# PiHat.net
KiCad netlist of a schematic drawn in EAGLE
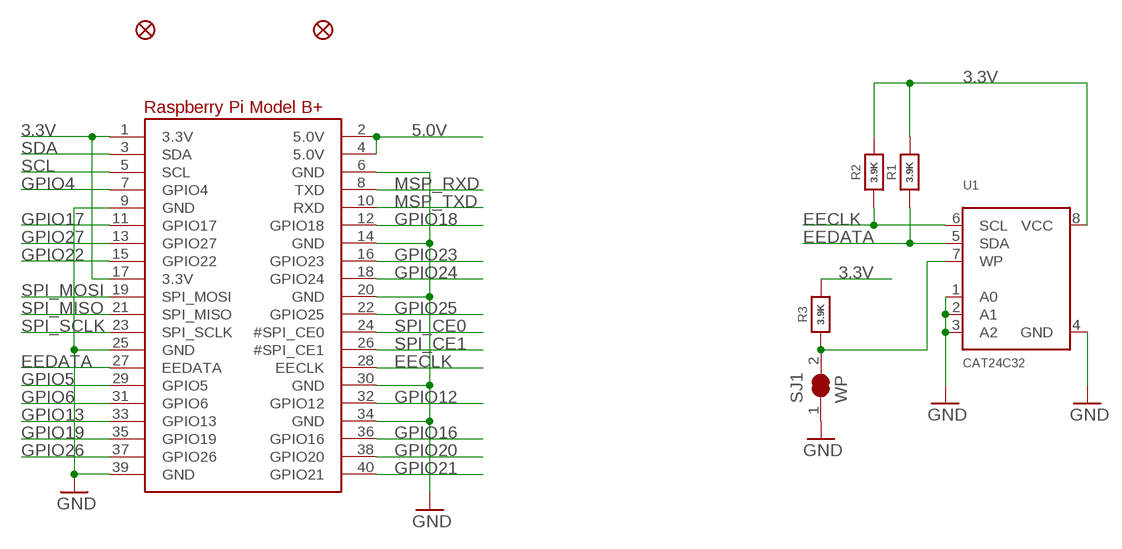
[diagram p0: schematic, sheet 1]
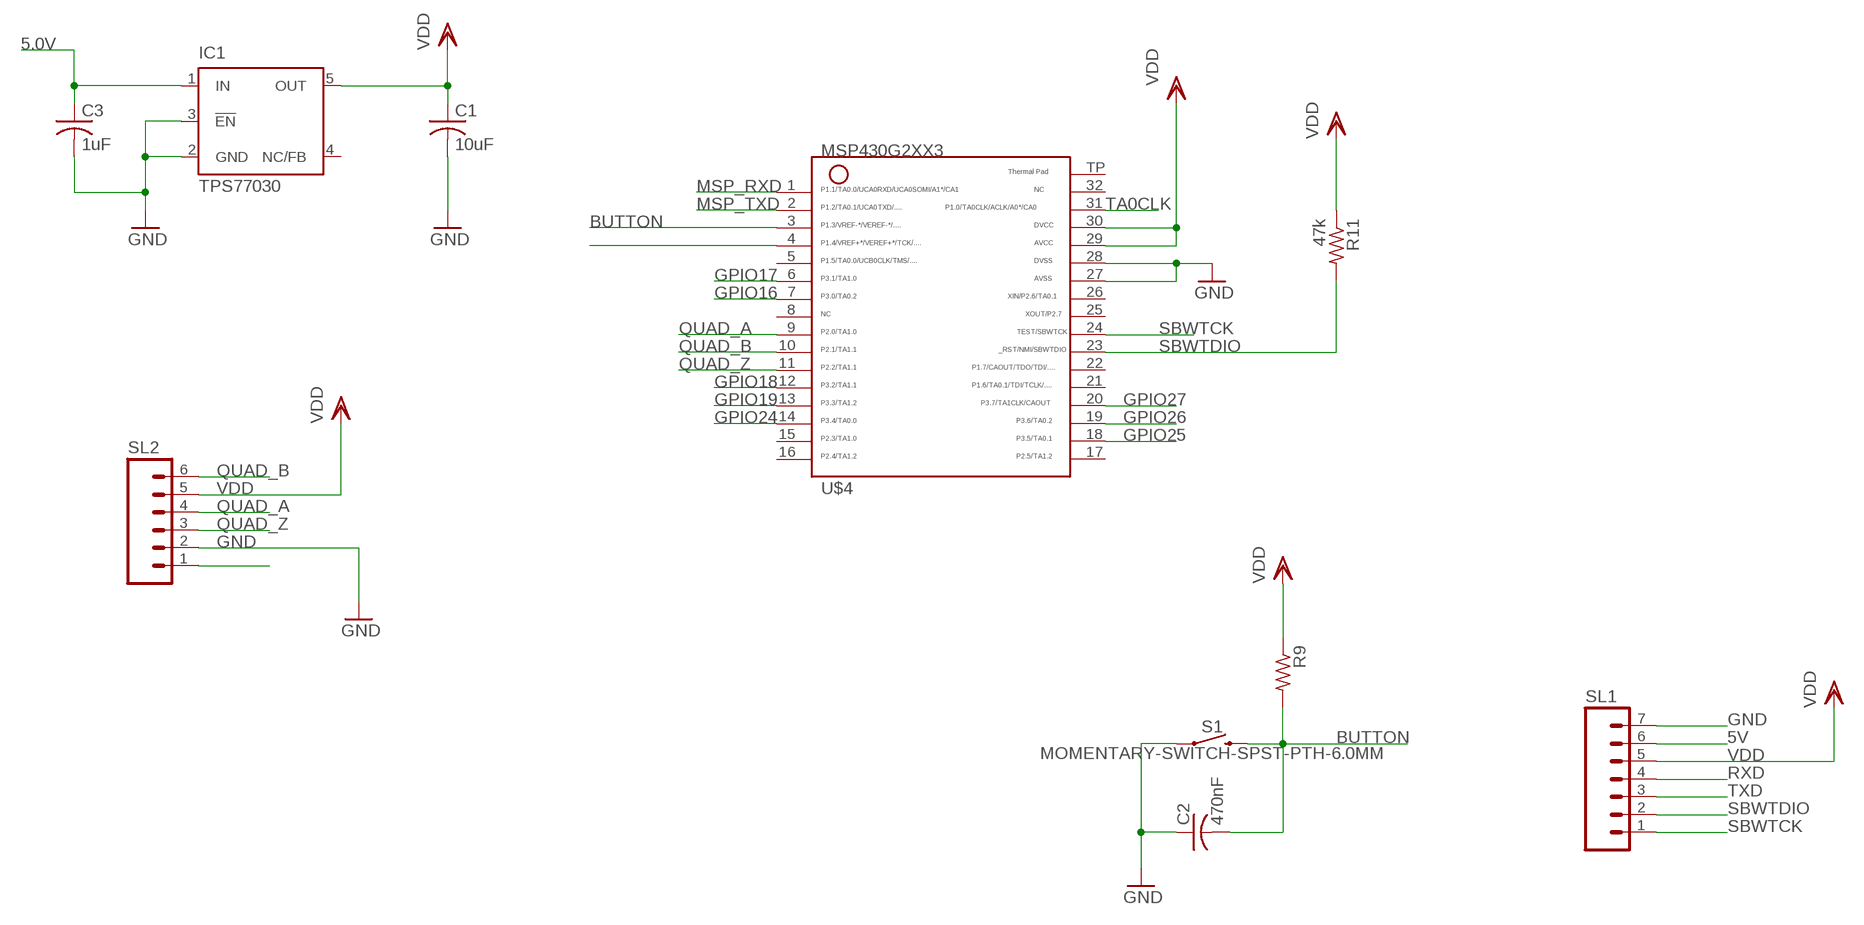
[diagram p1: schematic, sheet 2]

(export (version "E")
  (design (tool "Eeschema 10.0.6"))
  (components
    (comp (ref "FID2")
      (value "FIDUCIAL\"\"")
      (footprint "eagle-import:FIDUCIAL_1MM")
      (libsource (lib "eagle-import") (part "FIDUCIAL{dblquote}{dblquote}"))
    )
    (comp (ref "FID3")
      (value "FIDUCIAL\"\"")
      (footprint "eagle-import:FIDUCIAL_1MM")
      (libsource (lib "eagle-import") (part "FIDUCIAL{dblquote}{dblquote}"))
    )
    (comp (ref "R1")
      (value "3.9K")
      (footprint "eagle-import:0805-NO")
      (libsource (lib "eagle-import") (part "RESISTOR0805_NOOUTLINE"))
    )
    (comp (ref "R2")
      (value "3.9K")
      (footprint "eagle-import:0805-NO")
      (libsource (lib "eagle-import") (part "RESISTOR0805_NOOUTLINE"))
    )
    (comp (ref "R3")
      (value "3.9K")
      (footprint "eagle-import:0805-NO")
      (libsource (lib "eagle-import") (part "RESISTOR0805_NOOUTLINE"))
    )
    (comp (ref "RPI1")
      (value "RASPBERRYPI_BPLUS_HATNOSLOTS")
      (footprint "eagle-import:PI_HAT_NOSLOTS")
      (libsource (lib "eagle-import") (part "RASPBERRYPI_BPLUS_HATNOSLOTS"))
    )
    (comp (ref "SJ1")
      (value "WP")
      (footprint "eagle-import:SOLDERJUMPER_CLOSEDWIRE")
      (libsource (lib "eagle-import") (part "SOLDERJUMPER_CLOSED"))
    )
    (comp (ref "U1")
      (value "CAT24C32")
      (footprint "eagle-import:SOIC8_150MIL")
      (libsource (lib "eagle-import") (part "EEPROM_I2C_SOIC8_GENERIC"))
    )
    (comp (ref "C1")
      (value "10uF")
      (footprint "eagle-import:C1206")
      (libsource (lib "eagle-import") (part "C-USC1206"))
    )
    (comp (ref "C2")
      (value "470nF")
      (footprint "eagle-import:C1206")
      (libsource (lib "eagle-import") (part "C-USC1206"))
    )
    (comp (ref "C3")
      (value "1uF")
      (footprint "eagle-import:C0603")
      (libsource (lib "eagle-import") (part "C-USC0603"))
    )
    (comp (ref "IC1")
      (value "TPS77030")
      (footprint "eagle-import:SOT23-DBV")
      (fields (field (name "MF") "TEXAS INSTRUMENTS") (field (name "MPN") "TPS77030DBVT"))
      (libsource (lib "eagle-import") (part "TPS77030"))
    )
    (comp (ref "R9")
      (value "R-US_R1206")
      (footprint "eagle-import:R1206")
      (libsource (lib "eagle-import") (part "R-US_R1206"))
    )
    (comp (ref "R11")
      (value "47k")
      (footprint "eagle-import:R1206")
      (libsource (lib "eagle-import") (part "R-US_R1206"))
    )
    (comp (ref "S1")
      (value "MOMENTARY-SWITCH-SPST-PTH-6.0MM")
      (footprint "eagle-import:TACTILE_SWITCH_PTH_6.0MM")
      (libsource (lib "eagle-import") (part "MOMENTARY-SWITCH-SPST-PTH-6.0MM"))
    )
    (comp (ref "SL1")
      (value "M07")
      (footprint "eagle-import:07P")
      (libsource (lib "eagle-import") (part "M07"))
    )
    (comp (ref "SL2")
      (value "M06")
      (footprint "eagle-import:06P")
      (libsource (lib "eagle-import") (part "M06"))
    )
    (comp (ref "U$4")
      (value "G2XX3---RHB32")
      (footprint "eagle-import:RHB32")
      (libsource (lib "eagle-import") (part "G2XX3---RHB32"))
    )
  )
  (nets
    (net (code "1") (name "3.3V") (class "Default")
      (node (ref "R1") (pin "2") (pinfunction "2_2") (pintype "passive"))
      (node (ref "R2") (pin "2") (pinfunction "2_2") (pintype "passive"))
      (node (ref "R3") (pin "2") (pinfunction "2_2") (pintype "passive"))
      (node (ref "RPI1") (pin "1") (pinfunction "3.3V_1") (pintype "power_in"))
      (node (ref "RPI1") (pin "17") (pinfunction "3.3V_17") (pintype "power_in"))
      (node (ref "U1") (pin "8") (pinfunction "VCC_8") (pintype "power_in"))
    )
    (net (code "2") (name "5.0V") (class "Default")
      (node (ref "C3") (pin "1") (pinfunction "1_1") (pintype "passive"))
      (node (ref "IC1") (pin "1") (pinfunction "IN_1") (pintype "input"))
      (node (ref "RPI1") (pin "2") (pinfunction "5.0V_2") (pintype "power_in"))
      (node (ref "RPI1") (pin "4") (pinfunction "5.0V_4") (pintype "power_in"))
    )
    (net (code "3") (name "5V") (class "Default")
      (node (ref "SL1") (pin "6") (pinfunction "6_6") (pintype "passive"))
    )
    (net (code "4") (name "BUTTON") (class "Default")
      (node (ref "C2") (pin "2") (pinfunction "2_2") (pintype "passive"))
      (node (ref "R9") (pin "2") (pinfunction "2_2") (pintype "passive"))
      (node (ref "S1") (pin "3") (pinfunction "2_3") (pintype "passive"))
      (node (ref "U$4") (pin "3") (pinfunction "3_3") (pintype "bidirectional"))
    )
    (net (code "5") (name "EECLK") (class "Default")
      (node (ref "R2") (pin "1") (pinfunction "1_1") (pintype "passive"))
      (node (ref "RPI1") (pin "28") (pinfunction "EECLK_28") (pintype "power_in"))
      (node (ref "U1") (pin "6") (pinfunction "SCL_6") (pintype "input"))
    )
    (net (code "6") (name "EEDATA") (class "Default")
      (node (ref "R1") (pin "1") (pinfunction "1_1") (pintype "passive"))
      (node (ref "RPI1") (pin "27") (pinfunction "EEDATA_27") (pintype "bidirectional"))
      (node (ref "U1") (pin "5") (pinfunction "SDA_5") (pintype "bidirectional"))
    )
    (net (code "7") (name "GND") (class "Default")
      (node (ref "C1") (pin "2") (pinfunction "2_2") (pintype "passive"))
      (node (ref "C2") (pin "1") (pinfunction "1_1") (pintype "passive"))
      (node (ref "C3") (pin "2") (pinfunction "2_2") (pintype "passive"))
      (node (ref "IC1") (pin "2") (pinfunction "GND_2") (pintype "power_in"))
      (node (ref "IC1") (pin "3") (pinfunction "~{EN}_3") (pintype "input"))
      (node (ref "RPI1") (pin "14") (pinfunction "GND_14") (pintype "power_in"))
      (node (ref "RPI1") (pin "20") (pinfunction "GND_20") (pintype "power_in"))
      (node (ref "RPI1") (pin "25") (pinfunction "GND_25") (pintype "power_in"))
      (node (ref "RPI1") (pin "30") (pinfunction "GND_30") (pintype "bidirectional"))
      (node (ref "RPI1") (pin "34") (pinfunction "GND_34") (pintype "bidirectional"))
      (node (ref "RPI1") (pin "39") (pinfunction "GND_39") (pintype "power_in"))
      (node (ref "RPI1") (pin "6") (pinfunction "GND_6") (pintype "power_in"))
      (node (ref "RPI1") (pin "9") (pinfunction "GND_9") (pintype "power_in"))
      (node (ref "S1") (pin "1") (pinfunction "1_1") (pintype "passive"))
      (node (ref "SJ1") (pin "1") (pinfunction "1_1") (pintype "passive"))
      (node (ref "SL1") (pin "7") (pinfunction "7_7") (pintype "passive"))
      (node (ref "SL2") (pin "2") (pinfunction "2_2") (pintype "passive"))
      (node (ref "U$4") (pin "27") (pinfunction "27_27") (pintype "bidirectional"))
      (node (ref "U$4") (pin "28") (pinfunction "28_28") (pintype "bidirectional"))
      (node (ref "U1") (pin "1") (pinfunction "A0_1") (pintype "input"))
      (node (ref "U1") (pin "2") (pinfunction "A1_2") (pintype "input"))
      (node (ref "U1") (pin "3") (pinfunction "A2_3") (pintype "input"))
      (node (ref "U1") (pin "4") (pinfunction "GND_4") (pintype "power_in"))
    )
    (net (code "8") (name "GPIO4") (class "Default")
      (node (ref "RPI1") (pin "7") (pinfunction "GPIO4_7") (pintype "bidirectional"))
    )
    (net (code "9") (name "GPIO5") (class "Default")
      (node (ref "RPI1") (pin "29") (pinfunction "GPIO5_29") (pintype "bidirectional"))
    )
    (net (code "10") (name "GPIO6") (class "Default")
      (node (ref "RPI1") (pin "31") (pinfunction "GPIO6_31") (pintype "power_in"))
    )
    (net (code "11") (name "GPIO12") (class "Default")
      (node (ref "RPI1") (pin "32") (pinfunction "GPIO12_32") (pintype "bidirectional"))
    )
    (net (code "12") (name "GPIO13") (class "Default")
      (node (ref "RPI1") (pin "33") (pinfunction "GPIO13_33") (pintype "bidirectional"))
    )
    (net (code "13") (name "GPIO16") (class "Default")
      (node (ref "RPI1") (pin "36") (pinfunction "GPIO16_36") (pintype "power_in"))
      (node (ref "U$4") (pin "7") (pinfunction "7_7") (pintype "bidirectional"))
    )
    (net (code "14") (name "GPIO17") (class "Default")
      (node (ref "RPI1") (pin "11") (pinfunction "GPIO17_11") (pintype "bidirectional"))
      (node (ref "U$4") (pin "6") (pinfunction "6_6") (pintype "bidirectional"))
    )
    (net (code "15") (name "GPIO18") (class "Default")
      (node (ref "RPI1") (pin "12") (pinfunction "GPIO18_12") (pintype "bidirectional"))
      (node (ref "U$4") (pin "12") (pinfunction "12_12") (pintype "bidirectional"))
    )
    (net (code "16") (name "GPIO19") (class "Default")
      (node (ref "RPI1") (pin "35") (pinfunction "GPIO19_35") (pintype "bidirectional"))
      (node (ref "U$4") (pin "13") (pinfunction "13_13") (pintype "bidirectional"))
    )
    (net (code "17") (name "GPIO20") (class "Default")
      (node (ref "RPI1") (pin "38") (pinfunction "GPIO20_38") (pintype "bidirectional"))
    )
    (net (code "18") (name "GPIO21") (class "Default")
      (node (ref "RPI1") (pin "40") (pinfunction "GPIO21_40") (pintype "bidirectional"))
    )
    (net (code "19") (name "GPIO22") (class "Default")
      (node (ref "RPI1") (pin "15") (pinfunction "GPIO22_15") (pintype "bidirectional"))
    )
    (net (code "20") (name "GPIO23") (class "Default")
      (node (ref "RPI1") (pin "16") (pinfunction "GPIO23_16") (pintype "bidirectional"))
    )
    (net (code "21") (name "GPIO24") (class "Default")
      (node (ref "RPI1") (pin "18") (pinfunction "GPIO24_18") (pintype "bidirectional"))
      (node (ref "U$4") (pin "14") (pinfunction "14_14") (pintype "bidirectional"))
    )
    (net (code "22") (name "GPIO25") (class "Default")
      (node (ref "RPI1") (pin "22") (pinfunction "GPIO25_22") (pintype "bidirectional"))
      (node (ref "U$4") (pin "18") (pinfunction "18_18") (pintype "bidirectional"))
    )
    (net (code "23") (name "GPIO26") (class "Default")
      (node (ref "RPI1") (pin "37") (pinfunction "GPIO26_37") (pintype "bidirectional"))
      (node (ref "U$4") (pin "19") (pinfunction "19_19") (pintype "bidirectional"))
    )
    (net (code "24") (name "GPIO27") (class "Default")
      (node (ref "RPI1") (pin "13") (pinfunction "GPIO27_13") (pintype "bidirectional"))
      (node (ref "U$4") (pin "20") (pinfunction "20_20") (pintype "bidirectional"))
    )
    (net (code "25") (name "MSP_RXD") (class "Default")
      (node (ref "RPI1") (pin "8") (pinfunction "TXD_8") (pintype "output"))
      (node (ref "U$4") (pin "1") (pinfunction "1_1") (pintype "bidirectional"))
    )
    (net (code "26") (name "MSP_TXD") (class "Default")
      (node (ref "RPI1") (pin "10") (pinfunction "RXD_10") (pintype "bidirectional"))
      (node (ref "U$4") (pin "2") (pinfunction "2_2") (pintype "bidirectional"))
    )
    (net (code "27") (name "Net-(U1-WP)") (class "Default")
      (node (ref "R3") (pin "1") (pinfunction "1_1") (pintype "passive"))
      (node (ref "SJ1") (pin "2") (pinfunction "2_2") (pintype "passive"))
      (node (ref "U1") (pin "7") (pinfunction "WP_7") (pintype "input"))
    )
    (net (code "28") (name "QUAD_A") (class "Default")
      (node (ref "SL2") (pin "4") (pinfunction "4_4") (pintype "passive"))
      (node (ref "U$4") (pin "9") (pinfunction "9_9") (pintype "bidirectional"))
    )
    (net (code "29") (name "QUAD_B") (class "Default")
      (node (ref "SL2") (pin "6") (pinfunction "6_6") (pintype "passive"))
      (node (ref "U$4") (pin "10") (pinfunction "10_10") (pintype "bidirectional"))
    )
    (net (code "30") (name "QUAD_Z") (class "Default")
      (node (ref "SL2") (pin "3") (pinfunction "3_3") (pintype "passive"))
      (node (ref "U$4") (pin "11") (pinfunction "11_11") (pintype "bidirectional"))
    )
    (net (code "31") (name "RXD") (class "Default")
      (node (ref "SL1") (pin "4") (pinfunction "4_4") (pintype "passive"))
    )
    (net (code "32") (name "SBWTCK") (class "Default")
      (node (ref "SL1") (pin "1") (pinfunction "1_1") (pintype "passive"))
      (node (ref "U$4") (pin "24") (pinfunction "24_24") (pintype "bidirectional"))
    )
    (net (code "33") (name "SBWTDIO") (class "Default")
      (node (ref "R11") (pin "2") (pinfunction "2_2") (pintype "passive"))
      (node (ref "SL1") (pin "2") (pinfunction "2_2") (pintype "passive"))
      (node (ref "U$4") (pin "23") (pinfunction "23_23") (pintype "bidirectional"))
    )
    (net (code "34") (name "SCL") (class "Default")
      (node (ref "RPI1") (pin "5") (pinfunction "SCL_5") (pintype "bidirectional"))
    )
    (net (code "35") (name "SDA") (class "Default")
      (node (ref "RPI1") (pin "3") (pinfunction "SDA_3") (pintype "bidirectional"))
    )
    (net (code "36") (name "SPI_CE0") (class "Default")
      (node (ref "RPI1") (pin "24") (pinfunction "#SPI_CE0_24") (pintype "bidirectional"))
    )
    (net (code "37") (name "SPI_CE1") (class "Default")
      (node (ref "RPI1") (pin "26") (pinfunction "#SPI_CE1_26") (pintype "bidirectional"))
    )
    (net (code "38") (name "SPI_MISO") (class "Default")
      (node (ref "RPI1") (pin "21") (pinfunction "SPI_MISO_21") (pintype "bidirectional"))
    )
    (net (code "39") (name "SPI_MOSI") (class "Default")
      (node (ref "RPI1") (pin "19") (pinfunction "SPI_MOSI_19") (pintype "bidirectional"))
    )
    (net (code "40") (name "SPI_SCLK") (class "Default")
      (node (ref "RPI1") (pin "23") (pinfunction "SPI_SCLK_23") (pintype "bidirectional"))
    )
    (net (code "41") (name "TA0CLK") (class "Default")
      (node (ref "U$4") (pin "31") (pinfunction "31_31") (pintype "bidirectional"))
    )
    (net (code "42") (name "TXD") (class "Default")
      (node (ref "SL1") (pin "3") (pinfunction "3_3") (pintype "passive"))
    )
    (net (code "43") (name "VDD") (class "Default")
      (node (ref "C1") (pin "1") (pinfunction "1_1") (pintype "passive"))
      (node (ref "IC1") (pin "5") (pinfunction "OUT_5") (pintype "passive"))
      (node (ref "R11") (pin "1") (pinfunction "1_1") (pintype "passive"))
      (node (ref "R9") (pin "1") (pinfunction "1_1") (pintype "passive"))
      (node (ref "SL1") (pin "5") (pinfunction "5_5") (pintype "passive"))
      (node (ref "SL2") (pin "5") (pinfunction "5_5") (pintype "passive"))
      (node (ref "U$4") (pin "29") (pinfunction "29_29") (pintype "bidirectional"))
      (node (ref "U$4") (pin "30") (pinfunction "30_30") (pintype "bidirectional"))
    )
    (net (code "44") (name "unconnected-(IC1-NC{slash}FB-Pad4)") (class "Default")
      (node (ref "IC1") (pin "4") (pinfunction "NC/FB_4") (pintype "passive"))
    )
    (net (code "45") (name "unconnected-(SL2-Pad1)") (class "Default")
      (node (ref "SL2") (pin "1") (pinfunction "1_1") (pintype "passive"))
    )
    (net (code "46") (name "unconnected-(U$4-Pad4)") (class "Default")
      (node (ref "U$4") (pin "4") (pinfunction "4_4") (pintype "bidirectional"))
    )
    (net (code "47") (name "unconnected-(U$4-Pad5)") (class "Default")
      (node (ref "U$4") (pin "5") (pinfunction "5_5") (pintype "bidirectional"))
    )
    (net (code "48") (name "unconnected-(U$4-Pad8)") (class "Default")
      (node (ref "U$4") (pin "8") (pinfunction "8_8") (pintype "bidirectional"))
    )
    (net (code "49") (name "unconnected-(U$4-Pad15)") (class "Default")
      (node (ref "U$4") (pin "15") (pinfunction "15_15") (pintype "bidirectional"))
    )
    (net (code "50") (name "unconnected-(U$4-Pad16)") (class "Default")
      (node (ref "U$4") (pin "16") (pinfunction "16_16") (pintype "bidirectional"))
    )
    (net (code "51") (name "unconnected-(U$4-Pad17)") (class "Default")
      (node (ref "U$4") (pin "17") (pinfunction "17_17") (pintype "bidirectional"))
    )
    (net (code "52") (name "unconnected-(U$4-Pad21)") (class "Default")
      (node (ref "U$4") (pin "21") (pinfunction "21_21") (pintype "bidirectional"))
    )
    (net (code "53") (name "unconnected-(U$4-Pad22)") (class "Default")
      (node (ref "U$4") (pin "22") (pinfunction "22_22") (pintype "bidirectional"))
    )
    (net (code "54") (name "unconnected-(U$4-Pad25)") (class "Default")
      (node (ref "U$4") (pin "25") (pinfunction "25_25") (pintype "bidirectional"))
    )
    (net (code "55") (name "unconnected-(U$4-Pad26)") (class "Default")
      (node (ref "U$4") (pin "26") (pinfunction "26_26") (pintype "bidirectional"))
    )
    (net (code "56") (name "unconnected-(U$4-Pad32)") (class "Default")
      (node (ref "U$4") (pin "32") (pinfunction "32_32") (pintype "bidirectional"))
    )
    (net (code "57") (name "unconnected-(U$4-PadTP)") (class "Default")
      (node (ref "U$4") (pin "TP") (pinfunction "TP_TP") (pintype "bidirectional"))
    )
  )
)
